# filters.net
KiCad netlist of a schematic drawn in EAGLE
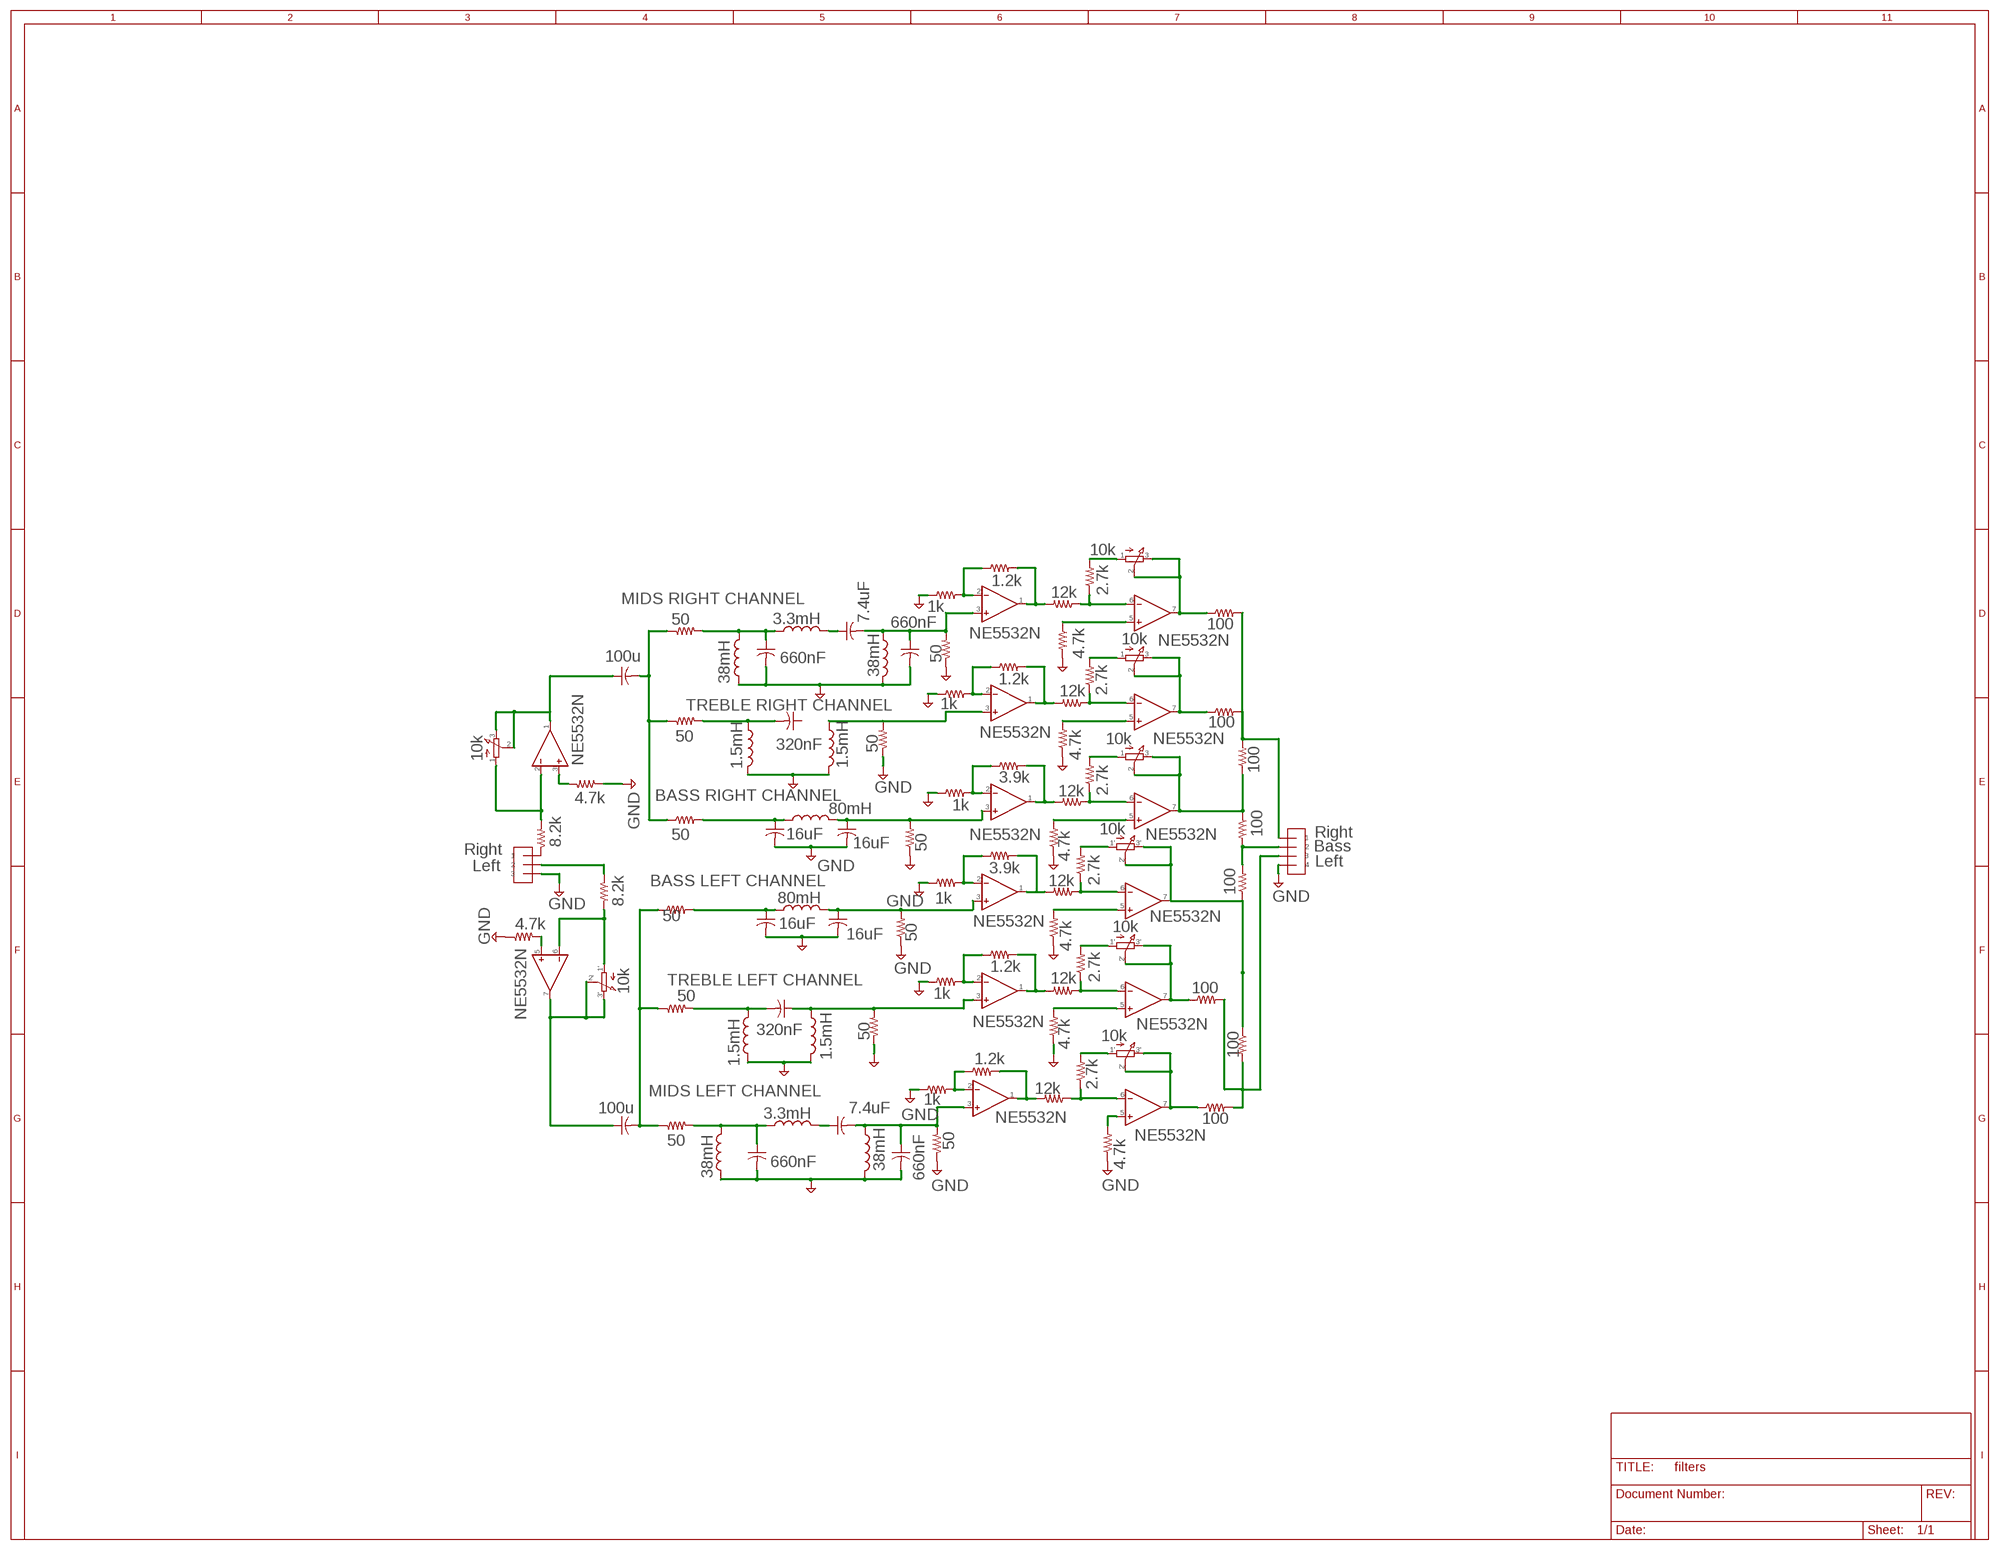
[diagram p0: schematic, sheet 1]

(export (version "E")
  (design (tool "Eeschema 10.0.6"))
  (components
    (comp (ref "C1")
      (value "7.4uF")
      (footprint "eagle-import:C050-024X044")
      (libsource (lib "eagle-import") (part "C-US050-024X044"))
    )
    (comp (ref "C2")
      (value "660nF")
      (footprint "eagle-import:C050-024X044")
      (libsource (lib "eagle-import") (part "C-US050-024X044"))
    )
    (comp (ref "C3")
      (value "660nF")
      (footprint "eagle-import:C050-024X044")
      (libsource (lib "eagle-import") (part "C-US050-024X044"))
    )
    (comp (ref "C4")
      (value "320nF")
      (footprint "eagle-import:C050-024X044")
      (libsource (lib "eagle-import") (part "C-US050-024X044"))
    )
    (comp (ref "C5")
      (value "16uF")
      (footprint "eagle-import:C050-024X044")
      (libsource (lib "eagle-import") (part "C-US050-024X044"))
    )
    (comp (ref "C6")
      (value "16uF")
      (footprint "eagle-import:C050-024X044")
      (libsource (lib "eagle-import") (part "C-US050-024X044"))
    )
    (comp (ref "C7")
      (value "16uF")
      (footprint "eagle-import:C050-024X044")
      (libsource (lib "eagle-import") (part "C-US050-024X044"))
    )
    (comp (ref "C8")
      (value "16uF")
      (footprint "eagle-import:C050-024X044")
      (libsource (lib "eagle-import") (part "C-US050-024X044"))
    )
    (comp (ref "C9")
      (value "320nF")
      (footprint "eagle-import:C050-024X044")
      (libsource (lib "eagle-import") (part "C-US050-024X044"))
    )
    (comp (ref "C10")
      (value "7.4uF")
      (footprint "eagle-import:C050-024X044")
      (libsource (lib "eagle-import") (part "C-US050-024X044"))
    )
    (comp (ref "C11")
      (value "660nF")
      (footprint "eagle-import:C050-024X044")
      (libsource (lib "eagle-import") (part "C-US050-024X044"))
    )
    (comp (ref "C12")
      (value "660nF")
      (footprint "eagle-import:C050-024X044")
      (libsource (lib "eagle-import") (part "C-US050-024X044"))
    )
    (comp (ref "C13")
      (value "100u")
      (footprint "eagle-import:C050-024X044")
      (libsource (lib "eagle-import") (part "C-US050-024X044"))
    )
    (comp (ref "C14")
      (value "100u")
      (footprint "eagle-import:C050-024X044")
      (libsource (lib "eagle-import") (part "C-US050-024X044"))
    )
    (comp (ref "IC1")
      (value "NE5532N")
      (footprint "eagle-import:DIL08")
      (libsource (lib "eagle-import") (part "NE5532N"))
    )
    (comp (ref "IC2")
      (value "NE5532N")
      (footprint "eagle-import:DIL08")
      (libsource (lib "eagle-import") (part "NE5532N"))
    )
    (comp (ref "IC3")
      (value "NE5532N")
      (footprint "eagle-import:DIL08")
      (libsource (lib "eagle-import") (part "NE5532N"))
    )
    (comp (ref "IC4")
      (value "NE5532N")
      (footprint "eagle-import:DIL08")
      (libsource (lib "eagle-import") (part "NE5532N"))
    )
    (comp (ref "IC5")
      (value "NE5532N")
      (footprint "eagle-import:DIL08")
      (libsource (lib "eagle-import") (part "NE5532N"))
    )
    (comp (ref "IC6")
      (value "NE5532N")
      (footprint "eagle-import:DIL08")
      (libsource (lib "eagle-import") (part "NE5532N"))
    )
    (comp (ref "IC7")
      (value "NE5532N")
      (footprint "eagle-import:DIL08")
      (libsource (lib "eagle-import") (part "NE5532N"))
    )
    (comp (ref "J1")
      (value "3_PIN_AMPCONN")
      (footprint "eagle-import:3_PIN_AMPCONN")
      (libsource (lib "eagle-import") (part "3_PIN_AMPCONN"))
    )
    (comp (ref "J2")
      (value "4_PIN_AMPCONN")
      (footprint "eagle-import:4_PIN_AMPCON")
      (libsource (lib "eagle-import") (part "4_PIN_AMPCONN"))
    )
    (comp (ref "L1")
      (value "3.3mH")
      (footprint "eagle-import:6000-XXXX-RC")
      (libsource (lib "eagle-import") (part "L-US6000-XXX-RC"))
    )
    (comp (ref "L2")
      (value "38mH")
      (footprint "eagle-import:6000-XXXX-RC")
      (libsource (lib "eagle-import") (part "L-US6000-XXX-RC"))
    )
    (comp (ref "L3")
      (value "38mH")
      (footprint "eagle-import:6000-XXXX-RC")
      (libsource (lib "eagle-import") (part "L-US6000-XXX-RC"))
    )
    (comp (ref "L4")
      (value "1.5mH")
      (footprint "eagle-import:6000-XXXX-RC")
      (libsource (lib "eagle-import") (part "L-US6000-XXX-RC"))
    )
    (comp (ref "L5")
      (value "1.5mH")
      (footprint "eagle-import:6000-XXXX-RC")
      (libsource (lib "eagle-import") (part "L-US6000-XXX-RC"))
    )
    (comp (ref "L6")
      (value "80mH")
      (footprint "eagle-import:6000-XXXX-RC")
      (libsource (lib "eagle-import") (part "L-US6000-XXX-RC"))
    )
    (comp (ref "L7")
      (value "80mH")
      (footprint "eagle-import:6000-XXXX-RC")
      (libsource (lib "eagle-import") (part "L-US6000-XXX-RC"))
    )
    (comp (ref "L8")
      (value "1.5mH")
      (footprint "eagle-import:6000-XXXX-RC")
      (libsource (lib "eagle-import") (part "L-US6000-XXX-RC"))
    )
    (comp (ref "L9")
      (value "1.5mH")
      (footprint "eagle-import:6000-XXXX-RC")
      (libsource (lib "eagle-import") (part "L-US6000-XXX-RC"))
    )
    (comp (ref "L10")
      (value "3.3mH")
      (footprint "eagle-import:6000-XXXX-RC")
      (libsource (lib "eagle-import") (part "L-US6000-XXX-RC"))
    )
    (comp (ref "L11")
      (value "38mH")
      (footprint "eagle-import:6000-XXXX-RC")
      (libsource (lib "eagle-import") (part "L-US6000-XXX-RC"))
    )
    (comp (ref "L12")
      (value "38mH")
      (footprint "eagle-import:6000-XXXX-RC")
      (libsource (lib "eagle-import") (part "L-US6000-XXX-RC"))
    )
    (comp (ref "R1")
      (value "8.2k")
      (footprint "eagle-import:0204V")
      (libsource (lib "eagle-import") (part "R-US_0204/2V"))
    )
    (comp (ref "R2")
      (value "8.2k")
      (footprint "eagle-import:0204V")
      (libsource (lib "eagle-import") (part "R-US_0204/2V"))
    )
    (comp (ref "R3")
      (value "50")
      (footprint "eagle-import:0204V")
      (libsource (lib "eagle-import") (part "R-US_0204/2V"))
    )
    (comp (ref "R4")
      (value "50")
      (footprint "eagle-import:0204V")
      (libsource (lib "eagle-import") (part "R-US_0204/2V"))
    )
    (comp (ref "R5")
      (value "1k")
      (footprint "eagle-import:0204V")
      (libsource (lib "eagle-import") (part "R-US_0204/2V"))
    )
    (comp (ref "R6")
      (value "12k")
      (footprint "eagle-import:0204V")
      (libsource (lib "eagle-import") (part "R-US_0204/2V"))
    )
    (comp (ref "R7")
      (value "1k")
      (footprint "eagle-import:0204V")
      (libsource (lib "eagle-import") (part "R-US_0204/2V"))
    )
    (comp (ref "R8")
      (value "3.9k")
      (footprint "eagle-import:0204V")
      (libsource (lib "eagle-import") (part "R-US_0204/2V"))
    )
    (comp (ref "R9")
      (value "50")
      (footprint "eagle-import:0204V")
      (libsource (lib "eagle-import") (part "R-US_0204/2V"))
    )
    (comp (ref "R10")
      (value "50")
      (footprint "eagle-import:0204V")
      (libsource (lib "eagle-import") (part "R-US_0204/2V"))
    )
    (comp (ref "R11")
      (value "12k")
      (footprint "eagle-import:0204V")
      (libsource (lib "eagle-import") (part "R-US_0204/2V"))
    )
    (comp (ref "R12")
      (value "1.2k")
      (footprint "eagle-import:0204V")
      (libsource (lib "eagle-import") (part "R-US_0204/2V"))
    )
    (comp (ref "R13")
      (value "1k")
      (footprint "eagle-import:0204V")
      (libsource (lib "eagle-import") (part "R-US_0204/2V"))
    )
    (comp (ref "R14")
      (value "50")
      (footprint "eagle-import:0204V")
      (libsource (lib "eagle-import") (part "R-US_0204/2V"))
    )
    (comp (ref "R15")
      (value "50")
      (footprint "eagle-import:0204V")
      (libsource (lib "eagle-import") (part "R-US_0204/2V"))
    )
    (comp (ref "R16")
      (value "12k")
      (footprint "eagle-import:0204V")
      (libsource (lib "eagle-import") (part "R-US_0204/2V"))
    )
    (comp (ref "R17")
      (value "1.2k")
      (footprint "eagle-import:0204V")
      (libsource (lib "eagle-import") (part "R-US_0204/2V"))
    )
    (comp (ref "R18")
      (value "2.7k")
      (footprint "eagle-import:0204V")
      (libsource (lib "eagle-import") (part "R-US_0204/2V"))
    )
    (comp (ref "R19")
      (value "12k")
      (footprint "eagle-import:0204V")
      (libsource (lib "eagle-import") (part "R-US_0204/2V"))
    )
    (comp (ref "R20")
      (value "1k")
      (footprint "eagle-import:0204V")
      (libsource (lib "eagle-import") (part "R-US_0204/2V"))
    )
    (comp (ref "R21")
      (value "3.9k")
      (footprint "eagle-import:0204V")
      (libsource (lib "eagle-import") (part "R-US_0204/2V"))
    )
    (comp (ref "R22")
      (value "50")
      (footprint "eagle-import:0204V")
      (libsource (lib "eagle-import") (part "R-US_0204/2V"))
    )
    (comp (ref "R23")
      (value "50")
      (footprint "eagle-import:0204V")
      (libsource (lib "eagle-import") (part "R-US_0204/2V"))
    )
    (comp (ref "R24")
      (value "12k")
      (footprint "eagle-import:0204V")
      (libsource (lib "eagle-import") (part "R-US_0204/2V"))
    )
    (comp (ref "R25")
      (value "1.2k")
      (footprint "eagle-import:0204V")
      (libsource (lib "eagle-import") (part "R-US_0204/2V"))
    )
    (comp (ref "R26")
      (value "1k")
      (footprint "eagle-import:0204V")
      (libsource (lib "eagle-import") (part "R-US_0204/2V"))
    )
    (comp (ref "R27")
      (value "50")
      (footprint "eagle-import:0204V")
      (libsource (lib "eagle-import") (part "R-US_0204/2V"))
    )
    (comp (ref "R28")
      (value "50")
      (footprint "eagle-import:0204V")
      (libsource (lib "eagle-import") (part "R-US_0204/2V"))
    )
    (comp (ref "R29")
      (value "2.7k")
      (footprint "eagle-import:0204V")
      (libsource (lib "eagle-import") (part "R-US_0204/2V"))
    )
    (comp (ref "R30")
      (value "2.7k")
      (footprint "eagle-import:0204V")
      (libsource (lib "eagle-import") (part "R-US_0204/2V"))
    )
    (comp (ref "R31")
      (value "50")
      (footprint "eagle-import:0204V")
      (libsource (lib "eagle-import") (part "R-US_0204/2V"))
    )
    (comp (ref "R32")
      (value "50")
      (footprint "eagle-import:0204V")
      (libsource (lib "eagle-import") (part "R-US_0204/2V"))
    )
    (comp (ref "R33")
      (value "12k")
      (footprint "eagle-import:0204V")
      (libsource (lib "eagle-import") (part "R-US_0204/2V"))
    )
    (comp (ref "R34")
      (value "2.7k")
      (footprint "eagle-import:0204V")
      (libsource (lib "eagle-import") (part "R-US_0204/2V"))
    )
    (comp (ref "R35")
      (value "2.7k")
      (footprint "eagle-import:0204V")
      (libsource (lib "eagle-import") (part "R-US_0204/2V"))
    )
    (comp (ref "R36")
      (value "1.2k")
      (footprint "eagle-import:0204V")
      (libsource (lib "eagle-import") (part "R-US_0204/2V"))
    )
    (comp (ref "R37")
      (value "2.7k")
      (footprint "eagle-import:0204V")
      (libsource (lib "eagle-import") (part "R-US_0204/2V"))
    )
    (comp (ref "R38")
      (value "1k")
      (footprint "eagle-import:0204V")
      (libsource (lib "eagle-import") (part "R-US_0204/2V"))
    )
    (comp (ref "R39")
      (value "100")
      (footprint "eagle-import:0204V")
      (libsource (lib "eagle-import") (part "R-US_0204/2V"))
    )
    (comp (ref "R40")
      (value "100")
      (footprint "eagle-import:0204V")
      (libsource (lib "eagle-import") (part "R-US_0204/2V"))
    )
    (comp (ref "R41")
      (value "100")
      (footprint "eagle-import:0204V")
      (libsource (lib "eagle-import") (part "R-US_0204/2V"))
    )
    (comp (ref "R42")
      (value "4.7k")
      (footprint "eagle-import:0204V")
      (libsource (lib "eagle-import") (part "R-US_0204/2V"))
    )
    (comp (ref "R43")
      (value "4.7k")
      (footprint "eagle-import:0204V")
      (libsource (lib "eagle-import") (part "R-US_0204/2V"))
    )
    (comp (ref "R44")
      (value "4.7k")
      (footprint "eagle-import:0204V")
      (libsource (lib "eagle-import") (part "R-US_0204/2V"))
    )
    (comp (ref "R45")
      (value "4.7k")
      (footprint "eagle-import:0204V")
      (libsource (lib "eagle-import") (part "R-US_0204/2V"))
    )
    (comp (ref "R46")
      (value "4.7k")
      (footprint "eagle-import:0204V")
      (libsource (lib "eagle-import") (part "R-US_0204/2V"))
    )
    (comp (ref "R47")
      (value "4.7k")
      (footprint "eagle-import:0204V")
      (libsource (lib "eagle-import") (part "R-US_0204/2V"))
    )
    (comp (ref "R48")
      (value "4.7k")
      (footprint "eagle-import:0204V")
      (libsource (lib "eagle-import") (part "R-US_0204/2V"))
    )
    (comp (ref "R49")
      (value "4.7k")
      (footprint "eagle-import:0204V")
      (libsource (lib "eagle-import") (part "R-US_0204/2V"))
    )
    (comp (ref "R88")
      (value "100")
      (footprint "eagle-import:0204V")
      (libsource (lib "eagle-import") (part "R-US_0204/2V"))
    )
    (comp (ref "R89")
      (value "100")
      (footprint "eagle-import:0204V")
      (libsource (lib "eagle-import") (part "R-US_0204/2V"))
    )
    (comp (ref "R90")
      (value "100")
      (footprint "eagle-import:0204V")
      (libsource (lib "eagle-import") (part "R-US_0204/2V"))
    )
    (comp (ref "R91")
      (value "100")
      (footprint "eagle-import:0204V")
      (libsource (lib "eagle-import") (part "R-US_0204/2V"))
    )
    (comp (ref "R92")
      (value "100")
      (footprint "eagle-import:0204V")
      (libsource (lib "eagle-import") (part "R-US_0204/2V"))
    )
    (comp (ref "VR1")
      (value "10k")
      (footprint "eagle-import:VOL_POT_2GANG")
      (libsource (lib "eagle-import") (part "VOL_POT_2GANG"))
    )
    (comp (ref "VR2")
      (value "10k")
      (footprint "eagle-import:TONE_POT_2GANG")
      (libsource (lib "eagle-import") (part "P140KV1-F25BR"))
    )
    (comp (ref "VR3")
      (value "10k")
      (footprint "eagle-import:TONE_POT_2GANG")
      (libsource (lib "eagle-import") (part "P140KV1-F25BR"))
    )
    (comp (ref "VR4")
      (value "10k")
      (footprint "eagle-import:TONE_POT_2GANG")
      (libsource (lib "eagle-import") (part "P140KV1-F25BR"))
    )
  )
  (nets
    (net (code "1") (name "GND") (class "Default")
      (node (ref "C11") (pin "2") (pinfunction "2_2") (pintype "passive"))
      (node (ref "C12") (pin "2") (pinfunction "2_2") (pintype "passive"))
      (node (ref "C2") (pin "2") (pinfunction "2_2") (pintype "passive"))
      (node (ref "C3") (pin "2") (pinfunction "2_2") (pintype "passive"))
      (node (ref "C5") (pin "2") (pinfunction "2_2") (pintype "passive"))
      (node (ref "C6") (pin "2") (pinfunction "2_2") (pintype "passive"))
      (node (ref "C7") (pin "2") (pinfunction "2_2") (pintype "passive"))
      (node (ref "C8") (pin "2") (pinfunction "2_2") (pintype "passive"))
      (node (ref "J1") (pin "3") (pinfunction "3_3") (pintype "passive"))
      (node (ref "J2") (pin "4") (pinfunction "4_4") (pintype "passive"))
      (node (ref "L11") (pin "2") (pinfunction "2_2") (pintype "passive"))
      (node (ref "L12") (pin "1") (pinfunction "1_1") (pintype "passive"))
      (node (ref "L2") (pin "1") (pinfunction "1_1") (pintype "passive"))
      (node (ref "L3") (pin "2") (pinfunction "2_2") (pintype "passive"))
      (node (ref "L4") (pin "2") (pinfunction "2_2") (pintype "passive"))
      (node (ref "L5") (pin "2") (pinfunction "2_2") (pintype "passive"))
      (node (ref "L8") (pin "1") (pinfunction "1_1") (pintype "passive"))
      (node (ref "L9") (pin "2") (pinfunction "2_2") (pintype "passive"))
      (node (ref "R10") (pin "1") (pinfunction "1_1") (pintype "passive"))
      (node (ref "R13") (pin "1") (pinfunction "1_1") (pintype "passive"))
      (node (ref "R15") (pin "1") (pinfunction "1_1") (pintype "passive"))
      (node (ref "R20") (pin "1") (pinfunction "1_1") (pintype "passive"))
      (node (ref "R23") (pin "1") (pinfunction "1_1") (pintype "passive"))
      (node (ref "R26") (pin "1") (pinfunction "1_1") (pintype "passive"))
      (node (ref "R28") (pin "1") (pinfunction "1_1") (pintype "passive"))
      (node (ref "R3") (pin "1") (pinfunction "1_1") (pintype "passive"))
      (node (ref "R31") (pin "1") (pinfunction "1_1") (pintype "passive"))
      (node (ref "R38") (pin "1") (pinfunction "1_1") (pintype "passive"))
      (node (ref "R42") (pin "1") (pinfunction "1_1") (pintype "passive"))
      (node (ref "R43") (pin "1") (pinfunction "1_1") (pintype "passive"))
      (node (ref "R44") (pin "2") (pinfunction "2_2") (pintype "passive"))
      (node (ref "R45") (pin "1") (pinfunction "1_1") (pintype "passive"))
      (node (ref "R46") (pin "1") (pinfunction "1_1") (pintype "passive"))
      (node (ref "R47") (pin "1") (pinfunction "1_1") (pintype "passive"))
      (node (ref "R48") (pin "1") (pinfunction "1_1") (pintype "passive"))
      (node (ref "R49") (pin "1") (pinfunction "1_1") (pintype "passive"))
      (node (ref "R5") (pin "1") (pinfunction "1_1") (pintype "passive"))
      (node (ref "R7") (pin "1") (pinfunction "1_1") (pintype "passive"))
    )
    (net (code "2") (name "Net-(C1-Pad1)") (class "Default")
      (node (ref "C1") (pin "1") (pinfunction "1_1") (pintype "passive"))
      (node (ref "L1") (pin "2") (pinfunction "2_2") (pintype "passive"))
    )
    (net (code "3") (name "Net-(C2-Pad1)") (class "Default")
      (node (ref "C2") (pin "1") (pinfunction "1_1") (pintype "passive"))
      (node (ref "L1") (pin "1") (pinfunction "1_1") (pintype "passive"))
      (node (ref "L2") (pin "2") (pinfunction "2_2") (pintype "passive"))
      (node (ref "R14") (pin "2") (pinfunction "2_2") (pintype "passive"))
    )
    (net (code "4") (name "Net-(C4-Pad2)") (class "Default")
      (node (ref "C4") (pin "2") (pinfunction "2_2") (pintype "passive"))
      (node (ref "L5") (pin "1") (pinfunction "1_1") (pintype "passive"))
      (node (ref "R9") (pin "2") (pinfunction "2_2") (pintype "passive"))
    )
    (net (code "5") (name "Net-(C5-Pad1)") (class "Default")
      (node (ref "C5") (pin "1") (pinfunction "1_1") (pintype "passive"))
      (node (ref "L6") (pin "1") (pinfunction "1_1") (pintype "passive"))
      (node (ref "R4") (pin "2") (pinfunction "2_2") (pintype "passive"))
    )
    (net (code "6") (name "Net-(C7-Pad1)") (class "Default")
      (node (ref "C7") (pin "1") (pinfunction "1_1") (pintype "passive"))
      (node (ref "L7") (pin "1") (pinfunction "1_1") (pintype "passive"))
      (node (ref "R32") (pin "2") (pinfunction "2_2") (pintype "passive"))
    )
    (net (code "7") (name "Net-(C9-Pad2)") (class "Default")
      (node (ref "C9") (pin "2") (pinfunction "2_2") (pintype "passive"))
      (node (ref "L8") (pin "2") (pinfunction "2_2") (pintype "passive"))
      (node (ref "R22") (pin "2") (pinfunction "2_2") (pintype "passive"))
    )
    (net (code "8") (name "Net-(C10-Pad1)") (class "Default")
      (node (ref "C10") (pin "1") (pinfunction "1_1") (pintype "passive"))
      (node (ref "L10") (pin "2") (pinfunction "2_2") (pintype "passive"))
    )
    (net (code "9") (name "Net-(C11-Pad1)") (class "Default")
      (node (ref "C11") (pin "1") (pinfunction "1_1") (pintype "passive"))
      (node (ref "L10") (pin "1") (pinfunction "1_1") (pintype "passive"))
      (node (ref "L12") (pin "2") (pinfunction "2_2") (pintype "passive"))
      (node (ref "R27") (pin "2") (pinfunction "2_2") (pintype "passive"))
    )
    (net (code "10") (name "Net-(C13-Pad2)") (class "Default")
      (node (ref "C13") (pin "2") (pinfunction "2_2") (pintype "passive"))
      (node (ref "R14") (pin "1") (pinfunction "1_1") (pintype "passive"))
      (node (ref "R4") (pin "1") (pinfunction "1_1") (pintype "passive"))
      (node (ref "R9") (pin "1") (pinfunction "1_1") (pintype "passive"))
    )
    (net (code "11") (name "Net-(C14-Pad2)") (class "Default")
      (node (ref "C14") (pin "2") (pinfunction "2_2") (pintype "passive"))
      (node (ref "R22") (pin "1") (pinfunction "1_1") (pintype "passive"))
      (node (ref "R27") (pin "1") (pinfunction "1_1") (pintype "passive"))
      (node (ref "R32") (pin "1") (pinfunction "1_1") (pintype "passive"))
    )
    (net (code "12") (name "Net-(IC1A-+IN)") (class "Default")
      (node (ref "IC1") (pin "3") (pinfunction "+IN_3") (pintype "input"))
      (node (ref "R42") (pin "2") (pinfunction "2_2") (pintype "passive"))
    )
    (net (code "13") (name "Net-(IC1A--IN)") (class "Default")
      (node (ref "IC1") (pin "2") (pinfunction "-IN_2") (pintype "input"))
      (node (ref "R1") (pin "2") (pinfunction "2_2") (pintype "passive"))
      (node (ref "VR1") (pin "1") (pinfunction "1_1") (pintype "passive"))
    )
    (net (code "14") (name "Net-(IC1A-OUT)") (class "Default")
      (node (ref "C13") (pin "1") (pinfunction "1_1") (pintype "passive"))
      (node (ref "IC1") (pin "1") (pinfunction "OUT_1") (pintype "output"))
      (node (ref "VR1") (pin "2") (pinfunction "2_2") (pintype "passive"))
      (node (ref "VR1") (pin "3") (pinfunction "3_3") (pintype "passive"))
    )
    (net (code "15") (name "Net-(IC1B-+IN)") (class "Default")
      (node (ref "IC1") (pin "5") (pinfunction "+IN_5") (pintype "input"))
      (node (ref "R43") (pin "2") (pinfunction "2_2") (pintype "passive"))
    )
    (net (code "16") (name "Net-(IC1B--IN)") (class "Default")
      (node (ref "IC1") (pin "6") (pinfunction "-IN_6") (pintype "input"))
      (node (ref "R2") (pin "2") (pinfunction "2_2") (pintype "passive"))
      (node (ref "VR1") (pin "1'") (pinfunction "1_1'") (pintype "passive"))
    )
    (net (code "17") (name "Net-(IC1B-OUT)") (class "Default")
      (node (ref "C14") (pin "1") (pinfunction "1_1") (pintype "passive"))
      (node (ref "IC1") (pin "7") (pinfunction "OUT_7") (pintype "output"))
      (node (ref "VR1") (pin "2'") (pinfunction "2_2'") (pintype "passive"))
      (node (ref "VR1") (pin "3'") (pinfunction "3_3'") (pintype "passive"))
    )
    (net (code "18") (name "Net-(IC2A-+IN)") (class "Default")
      (node (ref "C1") (pin "2") (pinfunction "2_2") (pintype "passive"))
      (node (ref "C3") (pin "1") (pinfunction "1_1") (pintype "passive"))
      (node (ref "IC2") (pin "3") (pinfunction "+IN_3") (pintype "input"))
      (node (ref "L3") (pin "1") (pinfunction "1_1") (pintype "passive"))
      (node (ref "R15") (pin "2") (pinfunction "2_2") (pintype "passive"))
    )
    (net (code "19") (name "Net-(IC2A--IN)") (class "Default")
      (node (ref "IC2") (pin "2") (pinfunction "-IN_2") (pintype "input"))
      (node (ref "R17") (pin "1") (pinfunction "1_1") (pintype "passive"))
      (node (ref "R5") (pin "2") (pinfunction "2_2") (pintype "passive"))
    )
    (net (code "20") (name "Net-(IC2A-OUT)") (class "Default")
      (node (ref "IC2") (pin "1") (pinfunction "OUT_1") (pintype "output"))
      (node (ref "R16") (pin "2") (pinfunction "2_2") (pintype "passive"))
      (node (ref "R17") (pin "2") (pinfunction "2_2") (pintype "passive"))
    )
    (net (code "21") (name "Net-(IC2B-+IN)") (class "Default")
      (node (ref "IC2") (pin "5") (pinfunction "+IN_5") (pintype "input"))
      (node (ref "R44") (pin "1") (pinfunction "1_1") (pintype "passive"))
    )
    (net (code "22") (name "Net-(IC2B--IN)") (class "Default")
      (node (ref "IC2") (pin "6") (pinfunction "-IN_6") (pintype "input"))
      (node (ref "R16") (pin "1") (pinfunction "1_1") (pintype "passive"))
      (node (ref "R18") (pin "1") (pinfunction "1_1") (pintype "passive"))
    )
    (net (code "23") (name "Net-(IC2B-OUT)") (class "Default")
      (node (ref "IC2") (pin "7") (pinfunction "OUT_7") (pintype "output"))
      (node (ref "R88") (pin "1") (pinfunction "1_1") (pintype "passive"))
      (node (ref "VR2") (pin "2") (pinfunction "1_2_2") (pintype "passive"))
      (node (ref "VR2") (pin "3") (pinfunction "1_3_3") (pintype "passive"))
    )
    (net (code "24") (name "Net-(IC3A-+IN)") (class "Default")
      (node (ref "C10") (pin "2") (pinfunction "2_2") (pintype "passive"))
      (node (ref "C12") (pin "1") (pinfunction "1_1") (pintype "passive"))
      (node (ref "IC3") (pin "3") (pinfunction "+IN_3") (pintype "input"))
      (node (ref "L11") (pin "1") (pinfunction "1_1") (pintype "passive"))
      (node (ref "R28") (pin "2") (pinfunction "2_2") (pintype "passive"))
    )
    (net (code "25") (name "Net-(IC3A--IN)") (class "Default")
      (node (ref "IC3") (pin "2") (pinfunction "-IN_2") (pintype "input"))
      (node (ref "R36") (pin "1") (pinfunction "1_1") (pintype "passive"))
      (node (ref "R38") (pin "2") (pinfunction "2_2") (pintype "passive"))
    )
    (net (code "26") (name "Net-(IC3A-OUT)") (class "Default")
      (node (ref "IC3") (pin "1") (pinfunction "OUT_1") (pintype "output"))
      (node (ref "R33") (pin "2") (pinfunction "2_2") (pintype "passive"))
      (node (ref "R36") (pin "2") (pinfunction "2_2") (pintype "passive"))
    )
    (net (code "27") (name "Net-(IC3B-+IN)") (class "Default")
      (node (ref "IC3") (pin "5") (pinfunction "+IN_5") (pintype "input"))
      (node (ref "R49") (pin "2") (pinfunction "2_2") (pintype "passive"))
    )
    (net (code "28") (name "Net-(IC3B--IN)") (class "Default")
      (node (ref "IC3") (pin "6") (pinfunction "-IN_6") (pintype "input"))
      (node (ref "R33") (pin "1") (pinfunction "1_1") (pintype "passive"))
      (node (ref "R37") (pin "1") (pinfunction "1_1") (pintype "passive"))
    )
    (net (code "29") (name "Net-(IC3B-OUT)") (class "Default")
      (node (ref "IC3") (pin "7") (pinfunction "OUT_7") (pintype "output"))
      (node (ref "R92") (pin "1") (pinfunction "1_1") (pintype "passive"))
      (node (ref "VR2") (pin "2'") (pinfunction "1_2_2'") (pintype "passive"))
      (node (ref "VR2") (pin "3'") (pinfunction "1_3_3'") (pintype "passive"))
    )
    (net (code "30") (name "Net-(IC4A-+IN)") (class "Default")
      (node (ref "IC4") (pin "3") (pinfunction "+IN_3") (pintype "input"))
      (node (ref "L4") (pin "1") (pinfunction "1_1") (pintype "passive"))
      (node (ref "R10") (pin "2") (pinfunction "2_2") (pintype "passive"))
    )
    (net (code "31") (name "Net-(IC4A--IN)") (class "Default")
      (node (ref "IC4") (pin "2") (pinfunction "-IN_2") (pintype "input"))
      (node (ref "R12") (pin "1") (pinfunction "1_1") (pintype "passive"))
      (node (ref "R13") (pin "2") (pinfunction "2_2") (pintype "passive"))
    )
    (net (code "32") (name "Net-(IC4A-OUT)") (class "Default")
      (node (ref "IC4") (pin "1") (pinfunction "OUT_1") (pintype "output"))
      (node (ref "R11") (pin "2") (pinfunction "2_2") (pintype "passive"))
      (node (ref "R12") (pin "2") (pinfunction "2_2") (pintype "passive"))
    )
    (net (code "33") (name "Net-(IC4B-+IN)") (class "Default")
      (node (ref "IC4") (pin "5") (pinfunction "+IN_5") (pintype "input"))
      (node (ref "R45") (pin "2") (pinfunction "2_2") (pintype "passive"))
    )
    (net (code "34") (name "Net-(IC4B--IN)") (class "Default")
      (node (ref "IC4") (pin "6") (pinfunction "-IN_6") (pintype "input"))
      (node (ref "R11") (pin "1") (pinfunction "1_1") (pintype "passive"))
      (node (ref "R35") (pin "1") (pinfunction "1_1") (pintype "passive"))
    )
    (net (code "35") (name "Net-(IC4B-OUT)") (class "Default")
      (node (ref "IC4") (pin "7") (pinfunction "OUT_7") (pintype "output"))
      (node (ref "R89") (pin "1") (pinfunction "1_1") (pintype "passive"))
      (node (ref "VR3") (pin "2") (pinfunction "1_2_2") (pintype "passive"))
      (node (ref "VR3") (pin "3") (pinfunction "1_3_3") (pintype "passive"))
    )
    (net (code "36") (name "Net-(IC5A-+IN)") (class "Default")
      (node (ref "C9") (pin "1") (pinfunction "1_1") (pintype "passive"))
      (node (ref "IC5") (pin "3") (pinfunction "+IN_3") (pintype "input"))
      (node (ref "L9") (pin "1") (pinfunction "1_1") (pintype "passive"))
      (node (ref "R23") (pin "2") (pinfunction "2_2") (pintype "passive"))
    )
    (net (code "37") (name "Net-(IC5A--IN)") (class "Default")
      (node (ref "IC5") (pin "2") (pinfunction "-IN_2") (pintype "input"))
      (node (ref "R25") (pin "1") (pinfunction "1_1") (pintype "passive"))
      (node (ref "R26") (pin "2") (pinfunction "2_2") (pintype "passive"))
    )
    (net (code "38") (name "Net-(IC5A-OUT)") (class "Default")
      (node (ref "IC5") (pin "1") (pinfunction "OUT_1") (pintype "output"))
      (node (ref "R24") (pin "2") (pinfunction "2_2") (pintype "passive"))
      (node (ref "R25") (pin "2") (pinfunction "2_2") (pintype "passive"))
    )
    (net (code "39") (name "Net-(IC5B-+IN)") (class "Default")
      (node (ref "IC5") (pin "5") (pinfunction "+IN_5") (pintype "input"))
      (node (ref "R48") (pin "2") (pinfunction "2_2") (pintype "passive"))
    )
    (net (code "40") (name "Net-(IC5B--IN)") (class "Default")
      (node (ref "IC5") (pin "6") (pinfunction "-IN_6") (pintype "input"))
      (node (ref "R24") (pin "1") (pinfunction "1_1") (pintype "passive"))
      (node (ref "R30") (pin "1") (pinfunction "1_1") (pintype "passive"))
    )
    (net (code "41") (name "Net-(IC5B-OUT)") (class "Default")
      (node (ref "IC5") (pin "7") (pinfunction "OUT_7") (pintype "output"))
      (node (ref "R91") (pin "1") (pinfunction "1_1") (pintype "passive"))
      (node (ref "VR3") (pin "2'") (pinfunction "1_2_2'") (pintype "passive"))
      (node (ref "VR3") (pin "3'") (pinfunction "1_3_3'") (pintype "passive"))
    )
    (net (code "42") (name "Net-(IC6A-+IN)") (class "Default")
      (node (ref "C6") (pin "1") (pinfunction "1_1") (pintype "passive"))
      (node (ref "IC6") (pin "3") (pinfunction "+IN_3") (pintype "input"))
      (node (ref "L6") (pin "2") (pinfunction "2_2") (pintype "passive"))
      (node (ref "R3") (pin "2") (pinfunction "2_2") (pintype "passive"))
    )
    (net (code "43") (name "Net-(IC6A--IN)") (class "Default")
      (node (ref "IC6") (pin "2") (pinfunction "-IN_2") (pintype "input"))
      (node (ref "R7") (pin "2") (pinfunction "2_2") (pintype "passive"))
      (node (ref "R8") (pin "1") (pinfunction "1_1") (pintype "passive"))
    )
    (net (code "44") (name "Net-(IC6A-OUT)") (class "Default")
      (node (ref "IC6") (pin "1") (pinfunction "OUT_1") (pintype "output"))
      (node (ref "R6") (pin "2") (pinfunction "2_2") (pintype "passive"))
      (node (ref "R8") (pin "2") (pinfunction "2_2") (pintype "passive"))
    )
    (net (code "45") (name "Net-(IC6B-+IN)") (class "Default")
      (node (ref "IC6") (pin "5") (pinfunction "+IN_5") (pintype "input"))
      (node (ref "R46") (pin "2") (pinfunction "2_2") (pintype "passive"))
    )
    (net (code "46") (name "Net-(IC6B--IN)") (class "Default")
      (node (ref "IC6") (pin "6") (pinfunction "-IN_6") (pintype "input"))
      (node (ref "R34") (pin "1") (pinfunction "1_1") (pintype "passive"))
      (node (ref "R6") (pin "1") (pinfunction "1_1") (pintype "passive"))
    )
    (net (code "47") (name "Net-(IC6B-OUT)") (class "Default")
      (node (ref "IC6") (pin "7") (pinfunction "OUT_7") (pintype "output"))
      (node (ref "R40") (pin "1") (pinfunction "1_1") (pintype "passive"))
      (node (ref "R90") (pin "1") (pinfunction "1_1") (pintype "passive"))
      (node (ref "VR4") (pin "2") (pinfunction "1_2_2") (pintype "passive"))
      (node (ref "VR4") (pin "3") (pinfunction "1_3_3") (pintype "passive"))
    )
    (net (code "48") (name "Net-(IC7A-+IN)") (class "Default")
      (node (ref "C8") (pin "1") (pinfunction "1_1") (pintype "passive"))
      (node (ref "IC7") (pin "3") (pinfunction "+IN_3") (pintype "input"))
      (node (ref "L7") (pin "2") (pinfunction "2_2") (pintype "passive"))
      (node (ref "R31") (pin "2") (pinfunction "2_2") (pintype "passive"))
    )
    (net (code "49") (name "Net-(IC7A--IN)") (class "Default")
      (node (ref "IC7") (pin "2") (pinfunction "-IN_2") (pintype "input"))
      (node (ref "R20") (pin "2") (pinfunction "2_2") (pintype "passive"))
      (node (ref "R21") (pin "1") (pinfunction "1_1") (pintype "passive"))
    )
    (net (code "50") (name "Net-(IC7A-OUT)") (class "Default")
      (node (ref "IC7") (pin "1") (pinfunction "OUT_1") (pintype "output"))
      (node (ref "R19") (pin "2") (pinfunction "2_2") (pintype "passive"))
    )
    (net (code "51") (name "Net-(IC7B-+IN)") (class "Default")
      (node (ref "IC7") (pin "5") (pinfunction "+IN_5") (pintype "input"))
      (node (ref "R47") (pin "2") (pinfunction "2_2") (pintype "passive"))
    )
    (net (code "52") (name "Net-(IC7B--IN)") (class "Default")
      (node (ref "IC7") (pin "6") (pinfunction "-IN_6") (pintype "input"))
      (node (ref "R19") (pin "1") (pinfunction "1_1") (pintype "passive"))
      (node (ref "R29") (pin "1") (pinfunction "1_1") (pintype "passive"))
    )
    (net (code "53") (name "Net-(IC7B-OUT)") (class "Default")
      (node (ref "IC7") (pin "7") (pinfunction "OUT_7") (pintype "output"))
      (node (ref "R39") (pin "1") (pinfunction "1_1") (pintype "passive"))
      (node (ref "R41") (pin "1") (pinfunction "1_1") (pintype "passive"))
      (node (ref "VR4") (pin "2'") (pinfunction "1_2_2'") (pintype "passive"))
      (node (ref "VR4") (pin "3'") (pinfunction "1_3_3'") (pintype "passive"))
    )
    (net (code "54") (name "Net-(J1-Pad1)") (class "Default")
      (node (ref "J1") (pin "1") (pinfunction "1_1") (pintype "passive"))
      (node (ref "R1") (pin "1") (pinfunction "1_1") (pintype "passive"))
    )
    (net (code "55") (name "Net-(J1-Pad2)") (class "Default")
      (node (ref "J1") (pin "2") (pinfunction "2_2") (pintype "passive"))
      (node (ref "R2") (pin "1") (pinfunction "1_1") (pintype "passive"))
    )
    (net (code "56") (name "Net-(J2-Pad1)") (class "Default")
      (node (ref "J2") (pin "1") (pinfunction "1_1") (pintype "passive"))
      (node (ref "R40") (pin "2") (pinfunction "2_2") (pintype "passive"))
      (node (ref "R88") (pin "2") (pinfunction "2_2") (pintype "passive"))
      (node (ref "R89") (pin "2") (pinfunction "2_2") (pintype "passive"))
    )
    (net (code "57") (name "Net-(J2-Pad2)") (class "Default")
      (node (ref "J2") (pin "2") (pinfunction "2_2") (pintype "passive"))
      (node (ref "R41") (pin "2") (pinfunction "2_2") (pintype "passive"))
      (node (ref "R90") (pin "2") (pinfunction "2_2") (pintype "passive"))
    )
    (net (code "58") (name "Net-(J2-Pad3)") (class "Default")
      (node (ref "J2") (pin "3") (pinfunction "3_3") (pintype "passive"))
      (node (ref "R39") (pin "2") (pinfunction "2_2") (pintype "passive"))
      (node (ref "R91") (pin "2") (pinfunction "2_2") (pintype "passive"))
      (node (ref "R92") (pin "2") (pinfunction "2_2") (pintype "passive"))
    )
    (net (code "59") (name "Net-(VR2A-1_1)") (class "Default")
      (node (ref "R18") (pin "2") (pinfunction "2_2") (pintype "passive"))
      (node (ref "VR2") (pin "1") (pinfunction "1_1_1") (pintype "passive"))
    )
    (net (code "60") (name "Net-(VR2B-1_1)") (class "Default")
      (node (ref "R37") (pin "2") (pinfunction "2_2") (pintype "passive"))
      (node (ref "VR2") (pin "1'") (pinfunction "1_1_1'") (pintype "passive"))
    )
    (net (code "61") (name "Net-(VR3A-1_1)") (class "Default")
      (node (ref "R35") (pin "2") (pinfunction "2_2") (pintype "passive"))
      (node (ref "VR3") (pin "1") (pinfunction "1_1_1") (pintype "passive"))
    )
    (net (code "62") (name "Net-(VR3B-1_1)") (class "Default")
      (node (ref "R30") (pin "2") (pinfunction "2_2") (pintype "passive"))
      (node (ref "VR3") (pin "1'") (pinfunction "1_1_1'") (pintype "passive"))
    )
    (net (code "63") (name "Net-(VR4A-1_1)") (class "Default")
      (node (ref "R34") (pin "2") (pinfunction "2_2") (pintype "passive"))
      (node (ref "VR4") (pin "1") (pinfunction "1_1_1") (pintype "passive"))
    )
    (net (code "64") (name "Net-(VR4B-1_1)") (class "Default")
      (node (ref "R29") (pin "2") (pinfunction "2_2") (pintype "passive"))
      (node (ref "VR4") (pin "1'") (pinfunction "1_1_1'") (pintype "passive"))
    )
    (net (code "65") (name "unconnected-(C4-Pad1)") (class "Default")
      (node (ref "C4") (pin "1") (pinfunction "1_1") (pintype "passive"))
    )
    (net (code "66") (name "unconnected-(R21-Pad2)") (class "Default")
      (node (ref "R21") (pin "2") (pinfunction "2_2") (pintype "passive"))
    )
  )
)
